# vco1_pots.net
KiCad netlist of a schematic drawn in EAGLE
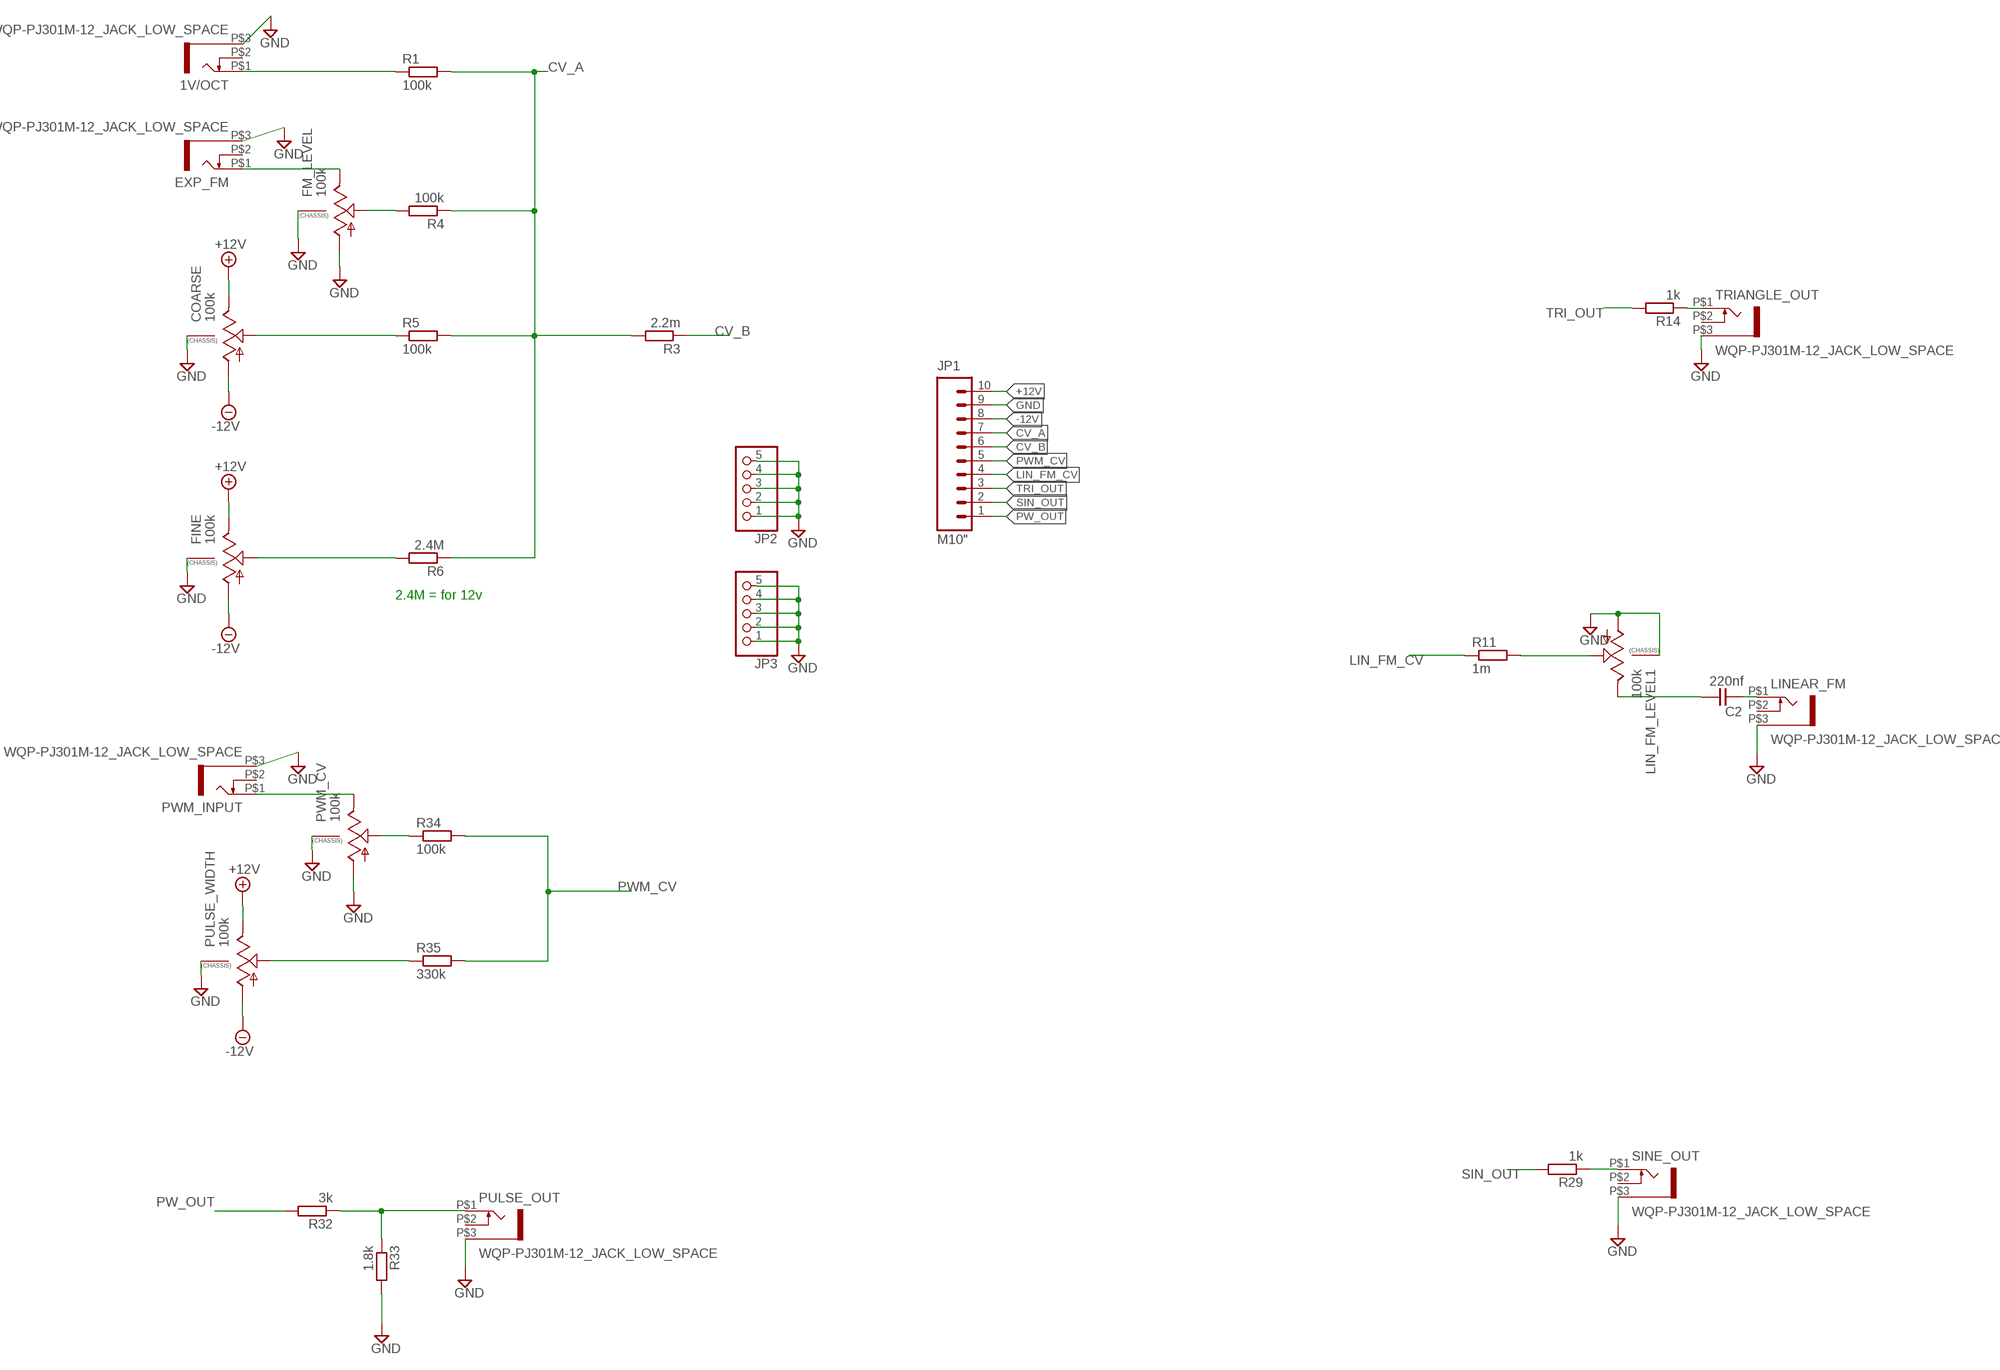
[diagram p0: schematic, sheet 1]

(export (version "E")
  (design (tool "Eeschema 10.0.6"))
  (components
    (comp (ref "1V/OCT")
      (value "WQP-PJ301M-12_JACK_LOW_SPACE")
      (footprint "eagle-import:WQP-PJ301M-12_JACK_LOW_SPACE")
      (libsource (lib "eagle-import") (part "WQP-PJ301M-12_JACK_LOW_SPACE"))
    )
    (comp (ref "C2")
      (value "220nf")
      (footprint "eagle-import:C050-024X044")
      (libsource (lib "eagle-import") (part "C-EU050-024X044"))
    )
    (comp (ref "COARSE")
      (value "100k")
      (footprint "eagle-import:9MM_SNAP-IN_POT")
      (libsource (lib "eagle-import") (part "9MM_SNAP-IN_POT_CHASSIS"))
    )
    (comp (ref "EXP_FM")
      (value "WQP-PJ301M-12_JACK_LOW_SPACE")
      (footprint "eagle-import:WQP-PJ301M-12_JACK_LOW_SPACE")
      (libsource (lib "eagle-import") (part "WQP-PJ301M-12_JACK_LOW_SPACE"))
    )
    (comp (ref "FINE")
      (value "100k")
      (footprint "eagle-import:9MM_SNAP-IN_POT")
      (libsource (lib "eagle-import") (part "9MM_SNAP-IN_POT_CHASSIS"))
    )
    (comp (ref "FM_LEVEL")
      (value "100k")
      (footprint "eagle-import:9MM_SNAP-IN_POT")
      (libsource (lib "eagle-import") (part "9MM_SNAP-IN_POT_CHASSIS"))
    )
    (comp (ref "JP1")
      (value "M10\"")
      (footprint "eagle-import:1X10")
      (libsource (lib "eagle-import") (part "M10{dblquote}"))
    )
    (comp (ref "JP2")
      (value "PINHD-1X55X2MM")
      (footprint "eagle-import:1_05X2MM")
      (libsource (lib "eagle-import") (part "PINHD-1X55X2MM"))
    )
    (comp (ref "JP3")
      (value "PINHD-1X55X2MM")
      (footprint "eagle-import:1_05X2MM")
      (libsource (lib "eagle-import") (part "PINHD-1X55X2MM"))
    )
    (comp (ref "LINEAR_FM")
      (value "WQP-PJ301M-12_JACK_LOW_SPACE")
      (footprint "eagle-import:WQP-PJ301M-12_JACK_LOW_SPACE")
      (libsource (lib "eagle-import") (part "WQP-PJ301M-12_JACK_LOW_SPACE"))
    )
    (comp (ref "LIN_FM_LEVEL1")
      (value "100k")
      (footprint "eagle-import:9MM_SNAP-IN_POT")
      (libsource (lib "eagle-import") (part "9MM_SNAP-IN_POT_CHASSIS"))
    )
    (comp (ref "PULSE_OUT")
      (value "WQP-PJ301M-12_JACK_LOW_SPACE")
      (footprint "eagle-import:WQP-PJ301M-12_JACK_LOW_SPACE")
      (libsource (lib "eagle-import") (part "WQP-PJ301M-12_JACK_LOW_SPACE"))
    )
    (comp (ref "PULSE_WIDTH")
      (value "100k")
      (footprint "eagle-import:9MM_SNAP-IN_POT")
      (libsource (lib "eagle-import") (part "9MM_SNAP-IN_POT_CHASSIS"))
    )
    (comp (ref "PWM_CV")
      (value "100k")
      (footprint "eagle-import:9MM_SNAP-IN_POT")
      (libsource (lib "eagle-import") (part "9MM_SNAP-IN_POT_CHASSIS"))
    )
    (comp (ref "PWM_INPUT")
      (value "WQP-PJ301M-12_JACK_LOW_SPACE")
      (footprint "eagle-import:WQP-PJ301M-12_JACK_LOW_SPACE")
      (libsource (lib "eagle-import") (part "WQP-PJ301M-12_JACK_LOW_SPACE"))
    )
    (comp (ref "R1")
      (value "100k")
      (footprint "eagle-import:7MM_RESISTOR")
      (libsource (lib "eagle-import") (part "RESISTOR7MM"))
    )
    (comp (ref "R3")
      (value "2.2m")
      (footprint "eagle-import:7MM_RESISTOR")
      (libsource (lib "eagle-import") (part "RESISTOR7MM"))
    )
    (comp (ref "R4")
      (value "100k")
      (footprint "eagle-import:7MM_RESISTOR")
      (libsource (lib "eagle-import") (part "RESISTOR7MM"))
    )
    (comp (ref "R5")
      (value "100k")
      (footprint "eagle-import:7MM_RESISTOR")
      (libsource (lib "eagle-import") (part "RESISTOR7MM"))
    )
    (comp (ref "R6")
      (value "2.4M")
      (footprint "eagle-import:7MM_RESISTOR")
      (libsource (lib "eagle-import") (part "RESISTOR7MM"))
    )
    (comp (ref "R11")
      (value "1m")
      (footprint "eagle-import:7MM_RESISTOR")
      (libsource (lib "eagle-import") (part "RESISTOR7MM"))
    )
    (comp (ref "R14")
      (value "1k")
      (footprint "eagle-import:7MM_RESISTOR")
      (libsource (lib "eagle-import") (part "RESISTOR7MM"))
    )
    (comp (ref "R29")
      (value "1k")
      (footprint "eagle-import:7MM_RESISTOR")
      (libsource (lib "eagle-import") (part "RESISTOR7MM"))
    )
    (comp (ref "R32")
      (value "3k")
      (footprint "eagle-import:7MM_RESISTOR")
      (libsource (lib "eagle-import") (part "RESISTOR7MM"))
    )
    (comp (ref "R33")
      (value "1.8k")
      (footprint "eagle-import:7MM_RESISTOR")
      (libsource (lib "eagle-import") (part "RESISTOR7MM"))
    )
    (comp (ref "R34")
      (value "100k")
      (footprint "eagle-import:7MM_RESISTOR")
      (libsource (lib "eagle-import") (part "RESISTOR7MM"))
    )
    (comp (ref "R35")
      (value "330k")
      (footprint "eagle-import:7MM_RESISTOR")
      (libsource (lib "eagle-import") (part "RESISTOR7MM"))
    )
    (comp (ref "SINE_OUT")
      (value "WQP-PJ301M-12_JACK_LOW_SPACE")
      (footprint "eagle-import:WQP-PJ301M-12_JACK_LOW_SPACE")
      (libsource (lib "eagle-import") (part "WQP-PJ301M-12_JACK_LOW_SPACE"))
    )
    (comp (ref "TRIANGLE_OUT")
      (value "WQP-PJ301M-12_JACK_LOW_SPACE")
      (footprint "eagle-import:WQP-PJ301M-12_JACK_LOW_SPACE")
      (libsource (lib "eagle-import") (part "WQP-PJ301M-12_JACK_LOW_SPACE"))
    )
  )
  (nets
    (net (code "1") (name "+12V") (class "Default")
      (node (ref "COARSE") (pin "3") (pinfunction "E_3") (pintype "passive"))
      (node (ref "FINE") (pin "3") (pinfunction "E_3") (pintype "passive"))
      (node (ref "JP1") (pin "10") (pinfunction "10_10") (pintype "passive"))
      (node (ref "PULSE_WIDTH") (pin "3") (pinfunction "E_3") (pintype "passive"))
    )
    (net (code "2") (name "-12V") (class "Default")
      (node (ref "COARSE") (pin "1") (pinfunction "A_1") (pintype "passive"))
      (node (ref "FINE") (pin "1") (pinfunction "A_1") (pintype "passive"))
      (node (ref "JP1") (pin "8") (pinfunction "8_8") (pintype "passive"))
      (node (ref "PULSE_WIDTH") (pin "1") (pinfunction "A_1") (pintype "passive"))
    )
    (net (code "3") (name "CV_A") (class "Default")
      (node (ref "JP1") (pin "7") (pinfunction "7_7") (pintype "passive"))
      (node (ref "R1") (pin "2") (pinfunction "2_2") (pintype "passive"))
      (node (ref "R3") (pin "2") (pinfunction "2_2") (pintype "passive"))
      (node (ref "R4") (pin "1") (pinfunction "1_1") (pintype "passive"))
      (node (ref "R5") (pin "2") (pinfunction "2_2") (pintype "passive"))
      (node (ref "R6") (pin "1") (pinfunction "1_1") (pintype "passive"))
    )
    (net (code "4") (name "CV_B") (class "Default")
      (node (ref "JP1") (pin "6") (pinfunction "6_6") (pintype "passive"))
      (node (ref "R3") (pin "1") (pinfunction "1_1") (pintype "passive"))
    )
    (net (code "5") (name "GND") (class "Default")
      (node (ref "1V/OCT") (pin "P$3") (pinfunction "1_P$3") (pintype "passive"))
      (node (ref "COARSE") (pin "CHASSIS2") (pinfunction "P$1_CHASSIS2") (pintype "passive"))
      (node (ref "EXP_FM") (pin "P$3") (pinfunction "1_P$3") (pintype "passive"))
      (node (ref "FINE") (pin "CHASSIS2") (pinfunction "P$1_CHASSIS2") (pintype "passive"))
      (node (ref "FM_LEVEL") (pin "1") (pinfunction "A_1") (pintype "passive"))
      (node (ref "FM_LEVEL") (pin "CHASSIS2") (pinfunction "P$1_CHASSIS2") (pintype "passive"))
      (node (ref "JP1") (pin "9") (pinfunction "9_9") (pintype "passive"))
      (node (ref "JP2") (pin "1") (pinfunction "1_1") (pintype "passive"))
      (node (ref "JP2") (pin "2") (pinfunction "2_2") (pintype "passive"))
      (node (ref "JP2") (pin "3") (pinfunction "3_3") (pintype "passive"))
      (node (ref "JP2") (pin "4") (pinfunction "4_4") (pintype "passive"))
      (node (ref "JP2") (pin "5") (pinfunction "5_5") (pintype "passive"))
      (node (ref "JP3") (pin "1") (pinfunction "1_1") (pintype "passive"))
      (node (ref "JP3") (pin "2") (pinfunction "2_2") (pintype "passive"))
      (node (ref "JP3") (pin "3") (pinfunction "3_3") (pintype "passive"))
      (node (ref "JP3") (pin "4") (pinfunction "4_4") (pintype "passive"))
      (node (ref "JP3") (pin "5") (pinfunction "5_5") (pintype "passive"))
      (node (ref "LINEAR_FM") (pin "P$3") (pinfunction "1_P$3") (pintype "passive"))
      (node (ref "LIN_FM_LEVEL1") (pin "1") (pinfunction "A_1") (pintype "passive"))
      (node (ref "LIN_FM_LEVEL1") (pin "CHASSIS2") (pinfunction "P$1_CHASSIS2") (pintype "passive"))
      (node (ref "PULSE_OUT") (pin "P$3") (pinfunction "1_P$3") (pintype "passive"))
      (node (ref "PULSE_WIDTH") (pin "CHASSIS2") (pinfunction "P$1_CHASSIS2") (pintype "passive"))
      (node (ref "PWM_CV") (pin "1") (pinfunction "A_1") (pintype "passive"))
      (node (ref "PWM_CV") (pin "CHASSIS2") (pinfunction "P$1_CHASSIS2") (pintype "passive"))
      (node (ref "PWM_INPUT") (pin "P$3") (pinfunction "1_P$3") (pintype "passive"))
      (node (ref "R33") (pin "2") (pinfunction "2_2") (pintype "passive"))
      (node (ref "SINE_OUT") (pin "P$3") (pinfunction "1_P$3") (pintype "passive"))
      (node (ref "TRIANGLE_OUT") (pin "P$3") (pinfunction "1_P$3") (pintype "passive"))
    )
    (net (code "6") (name "LIN_FM_CV") (class "Default")
      (node (ref "JP1") (pin "4") (pinfunction "4_4") (pintype "passive"))
      (node (ref "R11") (pin "1") (pinfunction "1_1") (pintype "passive"))
    )
    (net (code "7") (name "Net-(1V/OCT-2)") (class "Default")
      (node (ref "1V/OCT") (pin "P$1") (pinfunction "2_P$1") (pintype "passive"))
      (node (ref "R1") (pin "1") (pinfunction "1_1") (pintype "passive"))
    )
    (net (code "8") (name "Net-(COARSE-S)") (class "Default")
      (node (ref "COARSE") (pin "2") (pinfunction "S_2") (pintype "passive"))
      (node (ref "R5") (pin "1") (pinfunction "1_1") (pintype "passive"))
    )
    (net (code "9") (name "Net-(EXP_FM-2)") (class "Default")
      (node (ref "EXP_FM") (pin "P$1") (pinfunction "2_P$1") (pintype "passive"))
      (node (ref "FM_LEVEL") (pin "3") (pinfunction "E_3") (pintype "passive"))
    )
    (net (code "10") (name "Net-(FINE-S)") (class "Default")
      (node (ref "FINE") (pin "2") (pinfunction "S_2") (pintype "passive"))
      (node (ref "R6") (pin "2") (pinfunction "2_2") (pintype "passive"))
    )
    (net (code "11") (name "Net-(FM_LEVEL-S)") (class "Default")
      (node (ref "FM_LEVEL") (pin "2") (pinfunction "S_2") (pintype "passive"))
      (node (ref "R4") (pin "2") (pinfunction "2_2") (pintype "passive"))
    )
    (net (code "12") (name "Net-(LINEAR_FM-2)") (class "Default")
      (node (ref "C2") (pin "2") (pinfunction "2_2") (pintype "passive"))
      (node (ref "LINEAR_FM") (pin "P$1") (pinfunction "2_P$1") (pintype "passive"))
    )
    (net (code "13") (name "Net-(LIN_FM_LEVEL1-E)") (class "Default")
      (node (ref "C2") (pin "1") (pinfunction "1_1") (pintype "passive"))
      (node (ref "LIN_FM_LEVEL1") (pin "3") (pinfunction "E_3") (pintype "passive"))
    )
    (net (code "14") (name "Net-(LIN_FM_LEVEL1-S)") (class "Default")
      (node (ref "LIN_FM_LEVEL1") (pin "2") (pinfunction "S_2") (pintype "passive"))
      (node (ref "R11") (pin "2") (pinfunction "2_2") (pintype "passive"))
    )
    (net (code "15") (name "Net-(PULSE_OUT-2)") (class "Default")
      (node (ref "PULSE_OUT") (pin "P$1") (pinfunction "2_P$1") (pintype "passive"))
      (node (ref "R32") (pin "1") (pinfunction "1_1") (pintype "passive"))
      (node (ref "R33") (pin "1") (pinfunction "1_1") (pintype "passive"))
    )
    (net (code "16") (name "Net-(PULSE_WIDTH-S)") (class "Default")
      (node (ref "PULSE_WIDTH") (pin "2") (pinfunction "S_2") (pintype "passive"))
      (node (ref "R35") (pin "1") (pinfunction "1_1") (pintype "passive"))
    )
    (net (code "17") (name "Net-(PWM_CV-E)") (class "Default")
      (node (ref "PWM_CV") (pin "3") (pinfunction "E_3") (pintype "passive"))
      (node (ref "PWM_INPUT") (pin "P$1") (pinfunction "2_P$1") (pintype "passive"))
    )
    (net (code "18") (name "Net-(PWM_CV-S)") (class "Default")
      (node (ref "PWM_CV") (pin "2") (pinfunction "S_2") (pintype "passive"))
      (node (ref "R34") (pin "1") (pinfunction "1_1") (pintype "passive"))
    )
    (net (code "19") (name "Net-(SINE_OUT-2)") (class "Default")
      (node (ref "R29") (pin "1") (pinfunction "1_1") (pintype "passive"))
      (node (ref "SINE_OUT") (pin "P$1") (pinfunction "2_P$1") (pintype "passive"))
    )
    (net (code "20") (name "Net-(TRIANGLE_OUT-2)") (class "Default")
      (node (ref "R14") (pin "1") (pinfunction "1_1") (pintype "passive"))
      (node (ref "TRIANGLE_OUT") (pin "P$1") (pinfunction "2_P$1") (pintype "passive"))
    )
    (net (code "21") (name "PWM_CV") (class "Default")
      (node (ref "JP1") (pin "5") (pinfunction "5_5") (pintype "passive"))
      (node (ref "R34") (pin "2") (pinfunction "2_2") (pintype "passive"))
      (node (ref "R35") (pin "2") (pinfunction "2_2") (pintype "passive"))
    )
    (net (code "22") (name "PW_OUT") (class "Default")
      (node (ref "JP1") (pin "1") (pinfunction "1_1") (pintype "passive"))
      (node (ref "R32") (pin "2") (pinfunction "2_2") (pintype "passive"))
    )
    (net (code "23") (name "SIN_OUT") (class "Default")
      (node (ref "JP1") (pin "2") (pinfunction "2_2") (pintype "passive"))
      (node (ref "R29") (pin "2") (pinfunction "2_2") (pintype "passive"))
    )
    (net (code "24") (name "TRI_OUT") (class "Default")
      (node (ref "JP1") (pin "3") (pinfunction "3_3") (pintype "passive"))
      (node (ref "R14") (pin "2") (pinfunction "2_2") (pintype "passive"))
    )
    (net (code "25") (name "unconnected-(1V/OCT-3-PadP$2)") (class "Default")
      (node (ref "1V/OCT") (pin "P$2") (pinfunction "3_P$2") (pintype "passive"))
    )
    (net (code "26") (name "unconnected-(EXP_FM-3-PadP$2)") (class "Default")
      (node (ref "EXP_FM") (pin "P$2") (pinfunction "3_P$2") (pintype "passive"))
    )
    (net (code "27") (name "unconnected-(LINEAR_FM-3-PadP$2)") (class "Default")
      (node (ref "LINEAR_FM") (pin "P$2") (pinfunction "3_P$2") (pintype "passive"))
    )
    (net (code "28") (name "unconnected-(PULSE_OUT-3-PadP$2)") (class "Default")
      (node (ref "PULSE_OUT") (pin "P$2") (pinfunction "3_P$2") (pintype "passive"))
    )
    (net (code "29") (name "unconnected-(PWM_INPUT-3-PadP$2)") (class "Default")
      (node (ref "PWM_INPUT") (pin "P$2") (pinfunction "3_P$2") (pintype "passive"))
    )
    (net (code "30") (name "unconnected-(SINE_OUT-3-PadP$2)") (class "Default")
      (node (ref "SINE_OUT") (pin "P$2") (pinfunction "3_P$2") (pintype "passive"))
    )
    (net (code "31") (name "unconnected-(TRIANGLE_OUT-3-PadP$2)") (class "Default")
      (node (ref "TRIANGLE_OUT") (pin "P$2") (pinfunction "3_P$2") (pintype "passive"))
    )
  )
)
